# FeatherwingCircuitDual_autofocus.net
KiCad netlist of a schematic drawn in EAGLE
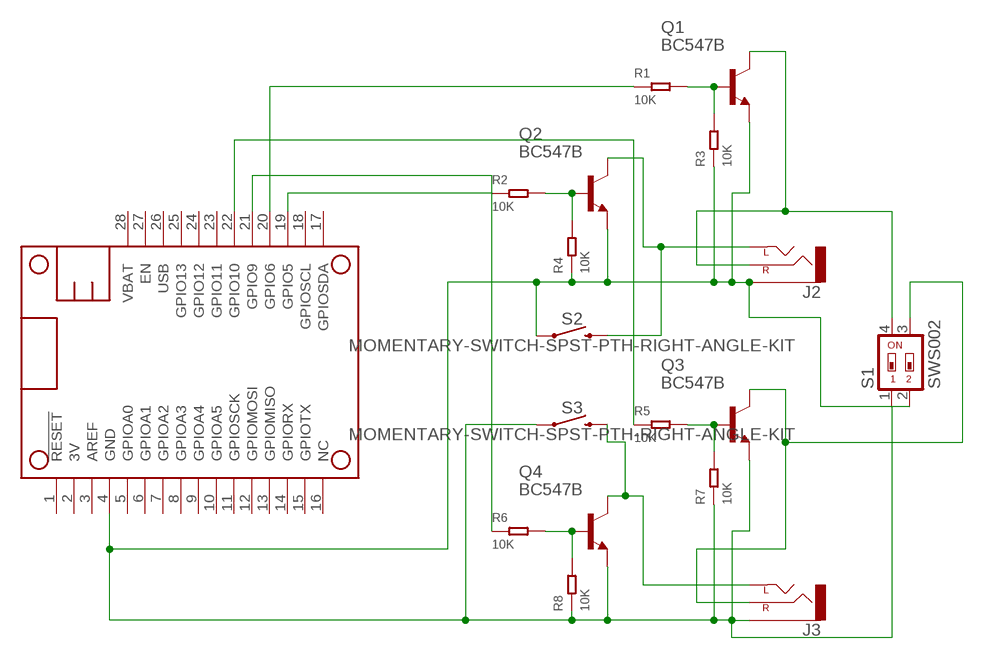
[diagram p0: schematic, sheet 1]

(export (version "E")
  (design (tool "Eeschema 10.0.6"))
  (components
    (comp (ref "J2")
      (value "AUDIO_JACK_2.5MM_2.5MM")
      (footprint "eagle-import:STEREOJACK2.5MM_STEREOJACK2.5MM")
      (libsource (lib "eagle-import") (part "AUDIO_JACK_2.5MM_2.5MM"))
    )
    (comp (ref "J3")
      (value "AUDIO_JACK_2.5MM_2.5MM")
      (footprint "eagle-import:STEREOJACK2.5MM_STEREOJACK2.5MM")
      (libsource (lib "eagle-import") (part "AUDIO_JACK_2.5MM_2.5MM"))
    )
    (comp (ref "MS1")
      (value "FEATHERWING_NODIM")
      (footprint "eagle-import:FEATHERWING_DIM")
      (libsource (lib "eagle-import") (part "FEATHERWING_NODIM"))
    )
    (comp (ref "Q1")
      (value "BC547B")
      (footprint "eagle-import:TO92")
      (libsource (lib "eagle-import") (part "BC547B"))
    )
    (comp (ref "Q2")
      (value "BC547B")
      (footprint "eagle-import:TO92")
      (libsource (lib "eagle-import") (part "BC547B"))
    )
    (comp (ref "Q3")
      (value "BC547B")
      (footprint "eagle-import:TO92")
      (libsource (lib "eagle-import") (part "BC547B"))
    )
    (comp (ref "Q4")
      (value "BC547B")
      (footprint "eagle-import:TO92")
      (libsource (lib "eagle-import") (part "BC547B"))
    )
    (comp (ref "R1")
      (value "10K")
      (footprint "eagle-import:PR-D2.3XL6.5MM")
      (fields (field (name "MPN") "FHCFR-1/4W-103J"))
      (libsource (lib "eagle-import") (part "DIP-RES-10K-5%-1/4W(PR-D2.3XL6.5MM)"))
    )
    (comp (ref "R2")
      (value "10K")
      (footprint "eagle-import:PR-D2.3XL6.5MM")
      (fields (field (name "MPN") "FHCFR-1/4W-103J"))
      (libsource (lib "eagle-import") (part "DIP-RES-10K-5%-1/4W(PR-D2.3XL6.5MM)"))
    )
    (comp (ref "R3")
      (value "10K")
      (footprint "eagle-import:PR-D2.3XL6.5MM")
      (fields (field (name "MPN") "FHCFR-1/4W-103J"))
      (libsource (lib "eagle-import") (part "DIP-RES-10K-5%-1/4W(PR-D2.3XL6.5MM)"))
    )
    (comp (ref "R4")
      (value "10K")
      (footprint "eagle-import:PR-D2.3XL6.5MM")
      (fields (field (name "MPN") "FHCFR-1/4W-103J"))
      (libsource (lib "eagle-import") (part "DIP-RES-10K-5%-1/4W(PR-D2.3XL6.5MM)"))
    )
    (comp (ref "R5")
      (value "10K")
      (footprint "eagle-import:PR-D2.3XL6.5MM")
      (fields (field (name "MPN") "FHCFR-1/4W-103J"))
      (libsource (lib "eagle-import") (part "DIP-RES-10K-5%-1/4W(PR-D2.3XL6.5MM)"))
    )
    (comp (ref "R6")
      (value "10K")
      (footprint "eagle-import:PR-D2.3XL6.5MM")
      (fields (field (name "MPN") "FHCFR-1/4W-103J"))
      (libsource (lib "eagle-import") (part "DIP-RES-10K-5%-1/4W(PR-D2.3XL6.5MM)"))
    )
    (comp (ref "R7")
      (value "10K")
      (footprint "eagle-import:PR-D2.3XL6.5MM")
      (fields (field (name "MPN") "FHCFR-1/4W-103J"))
      (libsource (lib "eagle-import") (part "DIP-RES-10K-5%-1/4W(PR-D2.3XL6.5MM)"))
    )
    (comp (ref "R8")
      (value "10K")
      (footprint "eagle-import:PR-D2.3XL6.5MM")
      (fields (field (name "MPN") "FHCFR-1/4W-103J"))
      (libsource (lib "eagle-import") (part "DIP-RES-10K-5%-1/4W(PR-D2.3XL6.5MM)"))
    )
    (comp (ref "S1")
      (value "SWS002")
      (footprint "eagle-import:SMS-002")
      (libsource (lib "eagle-import") (part "SWS002"))
    )
    (comp (ref "S2")
      (value "MOMENTARY-SWITCH-SPST-PTH-RIGHT-ANGLE-KIT")
      (footprint "eagle-import:TACTILE_SWITCH_PTH_RIGHT_ANGLE_KIT")
      (libsource (lib "eagle-import") (part "MOMENTARY-SWITCH-SPST-PTH-RIGHT-ANGLE-KIT"))
    )
    (comp (ref "S3")
      (value "MOMENTARY-SWITCH-SPST-PTH-RIGHT-ANGLE-KIT")
      (footprint "eagle-import:TACTILE_SWITCH_PTH_RIGHT_ANGLE_KIT")
      (libsource (lib "eagle-import") (part "MOMENTARY-SWITCH-SPST-PTH-RIGHT-ANGLE-KIT"))
    )
  )
  (nets
    (net (code "1") (name "/3V") (class "Default")
      (node (ref "MS1") (pin "2") (pinfunction "3V_2") (pintype "power_in"))
    )
    (net (code "2") (name "/USB") (class "Default")
      (node (ref "MS1") (pin "26") (pinfunction "USB_26") (pintype "power_in"))
    )
    (net (code "3") (name "/VBAT") (class "Default")
      (node (ref "MS1") (pin "28") (pinfunction "VBAT_28") (pintype "power_in"))
    )
    (net (code "4") (name "Net-(J2-LEFT)") (class "Default")
      (node (ref "J2") (pin "SHIELD") (pinfunction "LEFT_SHIELD") (pintype "bidirectional"))
      (node (ref "Q2") (pin "3") (pinfunction "C_3") (pintype "passive"))
      (node (ref "S2") (pin "2") (pinfunction "2_2") (pintype "passive"))
    )
    (net (code "5") (name "Net-(J2-RIGHT)") (class "Default")
      (node (ref "J2") (pin "TIP") (pinfunction "RIGHT_TIP") (pintype "bidirectional"))
      (node (ref "Q1") (pin "3") (pinfunction "C_3") (pintype "passive"))
      (node (ref "S1") (pin "4") (pinfunction "4_4") (pintype "passive"))
    )
    (net (code "6") (name "Net-(J2-SLEEVE)") (class "Default")
      (node (ref "J2") (pin "RING1") (pinfunction "SLEEVE_RING1") (pintype "bidirectional"))
      (node (ref "J3") (pin "RING1") (pinfunction "SLEEVE_RING1") (pintype "bidirectional"))
      (node (ref "MS1") (pin "4") (pinfunction "GND_4") (pintype "power_in"))
      (node (ref "Q1") (pin "1") (pinfunction "E_1") (pintype "passive"))
      (node (ref "Q2") (pin "1") (pinfunction "E_1") (pintype "passive"))
      (node (ref "Q3") (pin "1") (pinfunction "E_1") (pintype "passive"))
      (node (ref "Q4") (pin "1") (pinfunction "E_1") (pintype "passive"))
      (node (ref "R3") (pin "1") (pinfunction "1_1") (pintype "passive"))
      (node (ref "R4") (pin "1") (pinfunction "1_1") (pintype "passive"))
      (node (ref "R7") (pin "1") (pinfunction "1_1") (pintype "passive"))
      (node (ref "R8") (pin "1") (pinfunction "1_1") (pintype "passive"))
      (node (ref "S1") (pin "1") (pinfunction "1_1") (pintype "passive"))
      (node (ref "S1") (pin "2") (pinfunction "2_2") (pintype "passive"))
      (node (ref "S2") (pin "1") (pinfunction "1_1") (pintype "passive"))
      (node (ref "S3") (pin "1") (pinfunction "1_1") (pintype "passive"))
    )
    (net (code "7") (name "Net-(J3-LEFT)") (class "Default")
      (node (ref "J3") (pin "SHIELD") (pinfunction "LEFT_SHIELD") (pintype "bidirectional"))
      (node (ref "Q4") (pin "3") (pinfunction "C_3") (pintype "passive"))
      (node (ref "S3") (pin "2") (pinfunction "2_2") (pintype "passive"))
    )
    (net (code "8") (name "Net-(J3-RIGHT)") (class "Default")
      (node (ref "J3") (pin "TIP") (pinfunction "RIGHT_TIP") (pintype "bidirectional"))
      (node (ref "Q3") (pin "3") (pinfunction "C_3") (pintype "passive"))
      (node (ref "S1") (pin "3") (pinfunction "3_3") (pintype "passive"))
    )
    (net (code "9") (name "Net-(MS1-GPIO5)") (class "Default")
      (node (ref "MS1") (pin "19") (pinfunction "GPIO5_19") (pintype "bidirectional"))
      (node (ref "R2") (pin "1") (pinfunction "1_1") (pintype "passive"))
    )
    (net (code "10") (name "Net-(MS1-GPIO6)") (class "Default")
      (node (ref "MS1") (pin "20") (pinfunction "GPIO6_20") (pintype "bidirectional"))
      (node (ref "R1") (pin "1") (pinfunction "1_1") (pintype "passive"))
    )
    (net (code "11") (name "Net-(MS1-GPIO9)") (class "Default")
      (node (ref "MS1") (pin "21") (pinfunction "GPIO9_21") (pintype "bidirectional"))
      (node (ref "R6") (pin "1") (pinfunction "1_1") (pintype "passive"))
    )
    (net (code "12") (name "Net-(MS1-GPIO10)") (class "Default")
      (node (ref "MS1") (pin "22") (pinfunction "GPIO10_22") (pintype "bidirectional"))
      (node (ref "R5") (pin "1") (pinfunction "1_1") (pintype "passive"))
    )
    (net (code "13") (name "Net-(Q1-B)") (class "Default")
      (node (ref "Q1") (pin "2") (pinfunction "B_2") (pintype "passive"))
      (node (ref "R1") (pin "2") (pinfunction "2_2") (pintype "passive"))
      (node (ref "R3") (pin "2") (pinfunction "2_2") (pintype "passive"))
    )
    (net (code "14") (name "Net-(Q2-B)") (class "Default")
      (node (ref "Q2") (pin "2") (pinfunction "B_2") (pintype "passive"))
      (node (ref "R2") (pin "2") (pinfunction "2_2") (pintype "passive"))
      (node (ref "R4") (pin "2") (pinfunction "2_2") (pintype "passive"))
    )
    (net (code "15") (name "Net-(Q3-B)") (class "Default")
      (node (ref "Q3") (pin "2") (pinfunction "B_2") (pintype "passive"))
      (node (ref "R5") (pin "2") (pinfunction "2_2") (pintype "passive"))
      (node (ref "R7") (pin "2") (pinfunction "2_2") (pintype "passive"))
    )
    (net (code "16") (name "Net-(Q4-B)") (class "Default")
      (node (ref "Q4") (pin "2") (pinfunction "B_2") (pintype "passive"))
      (node (ref "R6") (pin "2") (pinfunction "2_2") (pintype "passive"))
      (node (ref "R8") (pin "2") (pinfunction "2_2") (pintype "passive"))
    )
    (net (code "17") (name "unconnected-(MS1-AREF-Pad3)") (class "Default")
      (node (ref "MS1") (pin "3") (pinfunction "AREF_3") (pintype "passive"))
    )
    (net (code "18") (name "unconnected-(MS1-EN-Pad27)") (class "Default")
      (node (ref "MS1") (pin "27") (pinfunction "EN_27") (pintype "passive"))
    )
    (net (code "19") (name "unconnected-(MS1-GPIO11-Pad23)") (class "Default")
      (node (ref "MS1") (pin "23") (pinfunction "GPIO11_23") (pintype "bidirectional"))
    )
    (net (code "20") (name "unconnected-(MS1-GPIO12-Pad24)") (class "Default")
      (node (ref "MS1") (pin "24") (pinfunction "GPIO12_24") (pintype "bidirectional"))
    )
    (net (code "21") (name "unconnected-(MS1-GPIO13-Pad25)") (class "Default")
      (node (ref "MS1") (pin "25") (pinfunction "GPIO13_25") (pintype "bidirectional"))
    )
    (net (code "22") (name "unconnected-(MS1-GPIOA0-Pad5)") (class "Default")
      (node (ref "MS1") (pin "5") (pinfunction "GPIOA0_5") (pintype "bidirectional"))
    )
    (net (code "23") (name "unconnected-(MS1-GPIOA1-Pad6)") (class "Default")
      (node (ref "MS1") (pin "6") (pinfunction "GPIOA1_6") (pintype "bidirectional"))
    )
    (net (code "24") (name "unconnected-(MS1-GPIOA2-Pad7)") (class "Default")
      (node (ref "MS1") (pin "7") (pinfunction "GPIOA2_7") (pintype "bidirectional"))
    )
    (net (code "25") (name "unconnected-(MS1-GPIOA3-Pad8)") (class "Default")
      (node (ref "MS1") (pin "8") (pinfunction "GPIOA3_8") (pintype "bidirectional"))
    )
    (net (code "26") (name "unconnected-(MS1-GPIOA4-Pad9)") (class "Default")
      (node (ref "MS1") (pin "9") (pinfunction "GPIOA4_9") (pintype "bidirectional"))
    )
    (net (code "27") (name "unconnected-(MS1-GPIOA5-Pad10)") (class "Default")
      (node (ref "MS1") (pin "10") (pinfunction "GPIOA5_10") (pintype "bidirectional"))
    )
    (net (code "28") (name "unconnected-(MS1-GPIOMISO-Pad13)") (class "Default")
      (node (ref "MS1") (pin "13") (pinfunction "GPIOMISO_13") (pintype "bidirectional"))
    )
    (net (code "29") (name "unconnected-(MS1-GPIOMOSI-Pad12)") (class "Default")
      (node (ref "MS1") (pin "12") (pinfunction "GPIOMOSI_12") (pintype "bidirectional"))
    )
    (net (code "30") (name "unconnected-(MS1-GPIORX-Pad14)") (class "Default")
      (node (ref "MS1") (pin "14") (pinfunction "GPIORX_14") (pintype "bidirectional"))
    )
    (net (code "31") (name "unconnected-(MS1-GPIOSCK-Pad11)") (class "Default")
      (node (ref "MS1") (pin "11") (pinfunction "GPIOSCK_11") (pintype "bidirectional"))
    )
    (net (code "32") (name "unconnected-(MS1-GPIOSCL-Pad18)") (class "Default")
      (node (ref "MS1") (pin "18") (pinfunction "GPIOSCL_18") (pintype "bidirectional"))
    )
    (net (code "33") (name "unconnected-(MS1-GPIOSDA-Pad17)") (class "Default")
      (node (ref "MS1") (pin "17") (pinfunction "GPIOSDA_17") (pintype "bidirectional"))
    )
    (net (code "34") (name "unconnected-(MS1-GPIOTX-Pad15)") (class "Default")
      (node (ref "MS1") (pin "15") (pinfunction "GPIOTX_15") (pintype "bidirectional"))
    )
    (net (code "35") (name "unconnected-(MS1-NC-Pad16)") (class "Default")
      (node (ref "MS1") (pin "16") (pinfunction "NC_16") (pintype "passive"))
    )
    (net (code "36") (name "unconnected-(MS1-~{RESET}-Pad1)") (class "Default")
      (node (ref "MS1") (pin "1") (pinfunction "~{RESET}_1") (pintype "input"))
    )
  )
)
